# Model01_ANAL.net
KiCad netlist of a schematic drawn in EAGLE
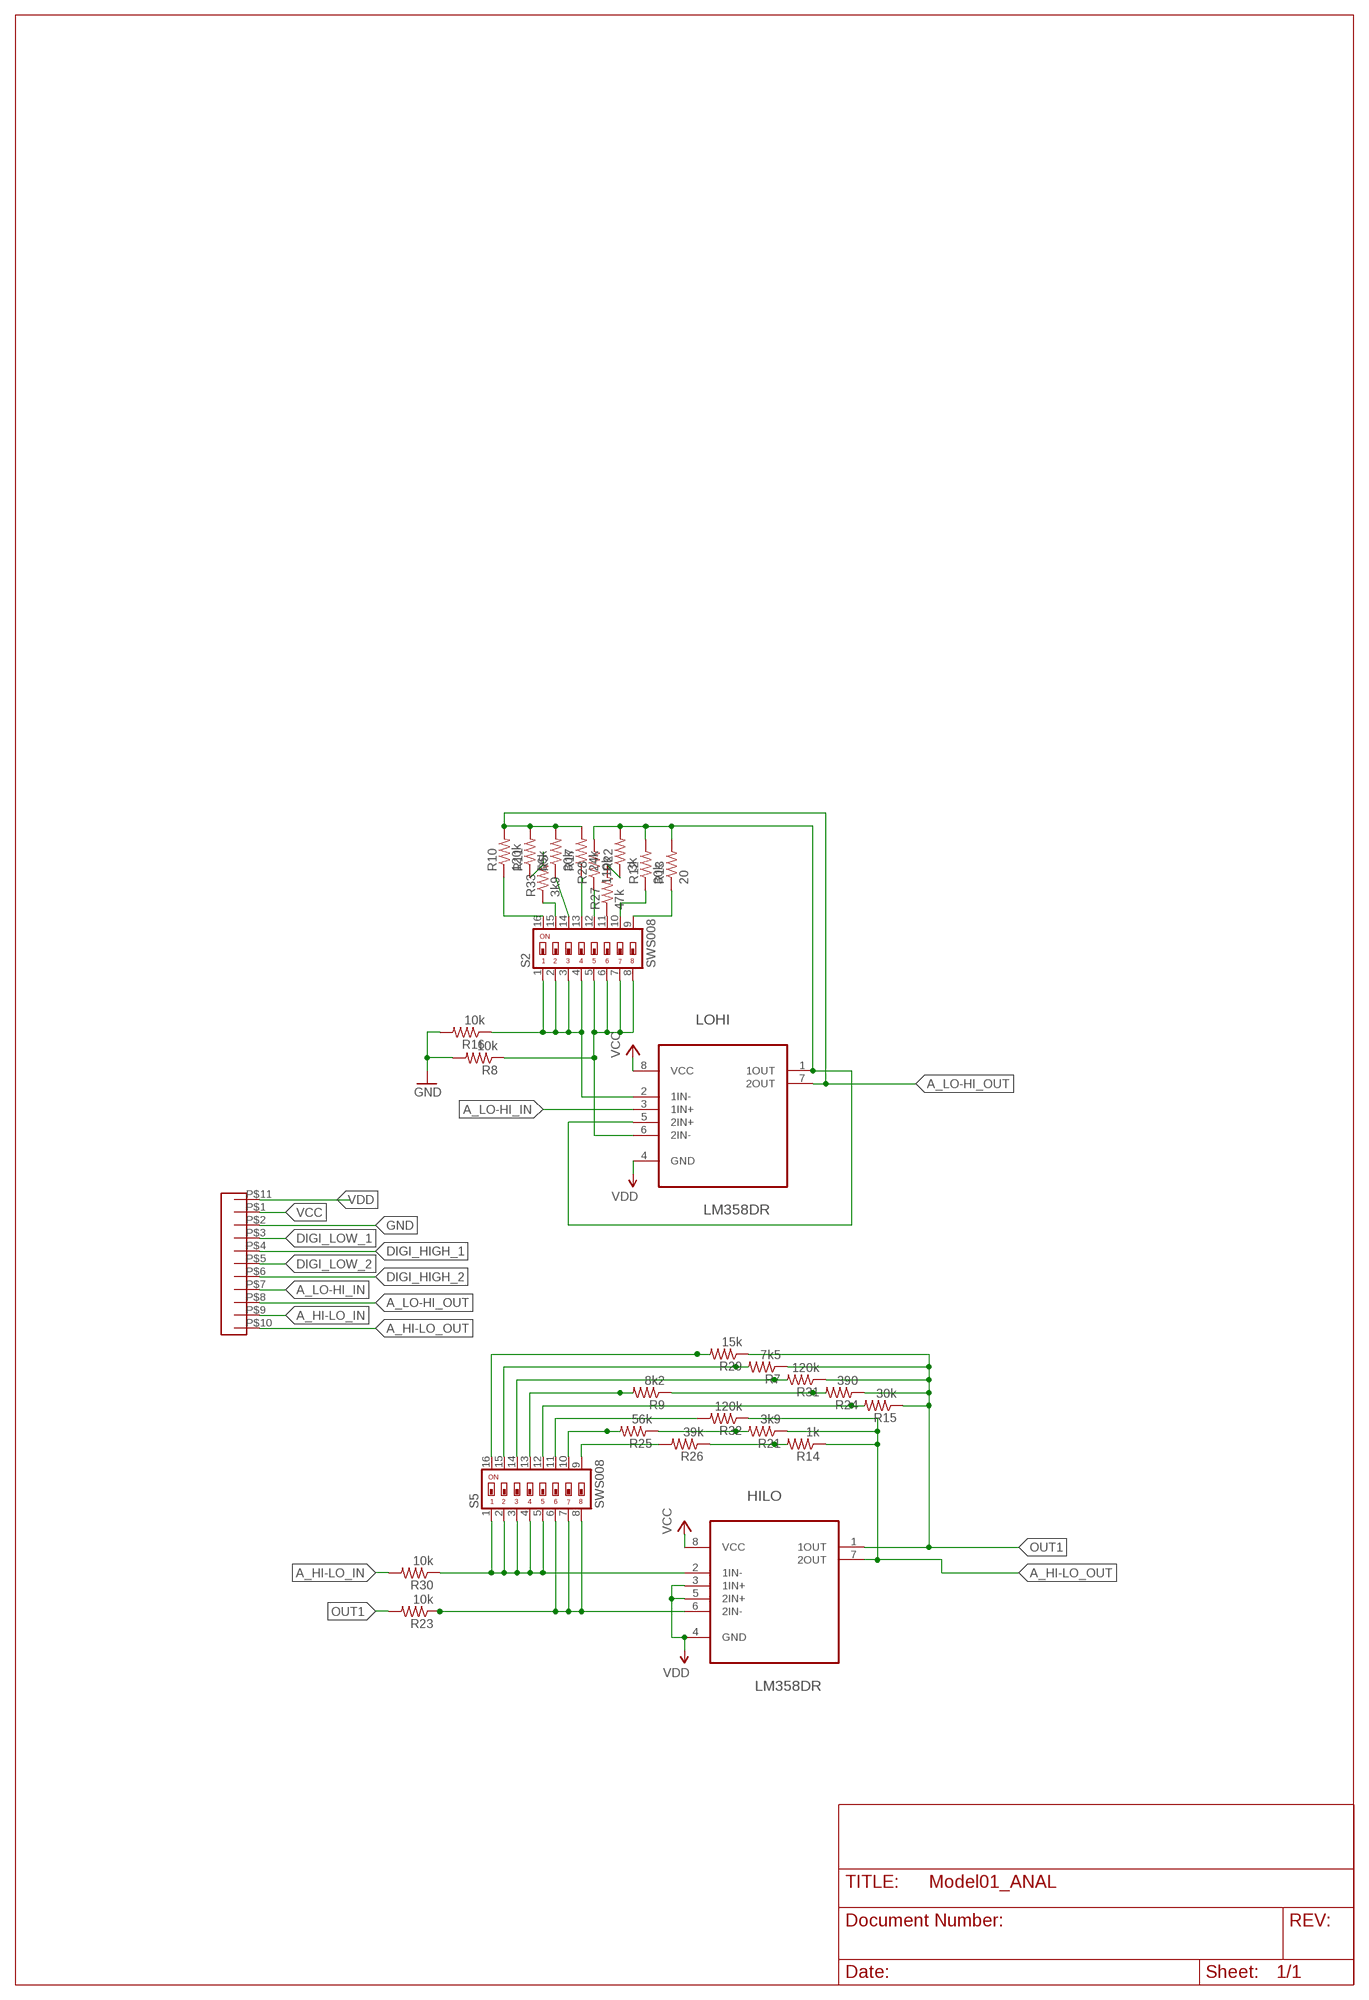
[diagram p0: schematic, sheet 1]

(export (version "E")
  (design (tool "Eeschema 10.0.6"))
  (components
    (comp (ref "HILO")
      (value "LM358DR")
      (footprint "eagle-import:SOIC127P600X175-8N")
      (libsource (lib "eagle-import") (part "LM358DR"))
    )
    (comp (ref "LOHI")
      (value "LM358DR")
      (footprint "eagle-import:SOIC127P600X175-8N")
      (libsource (lib "eagle-import") (part "LM358DR"))
    )
    (comp (ref "R5")
      (value "30k")
      (footprint "eagle-import:R0805")
      (libsource (lib "eagle-import") (part "R-US_R0805"))
    )
    (comp (ref "R7")
      (value "7k5")
      (footprint "eagle-import:R0805")
      (libsource (lib "eagle-import") (part "R-US_R0805"))
    )
    (comp (ref "R8")
      (value "10k")
      (footprint "eagle-import:R0805")
      (libsource (lib "eagle-import") (part "R-US_R0805"))
    )
    (comp (ref "R9")
      (value "8k2")
      (footprint "eagle-import:R0805")
      (libsource (lib "eagle-import") (part "R-US_R0805"))
    )
    (comp (ref "R10")
      (value "120k")
      (footprint "eagle-import:R0805")
      (libsource (lib "eagle-import") (part "R-US_R0805"))
    )
    (comp (ref "R11")
      (value "56k")
      (footprint "eagle-import:R0805")
      (libsource (lib "eagle-import") (part "R-US_R0805"))
    )
    (comp (ref "R12")
      (value "30k")
      (footprint "eagle-import:R0805")
      (libsource (lib "eagle-import") (part "R-US_R0805"))
    )
    (comp (ref "R13")
      (value "20")
      (footprint "eagle-import:R0805")
      (libsource (lib "eagle-import") (part "R-US_R0805"))
    )
    (comp (ref "R14")
      (value "1k")
      (footprint "eagle-import:R0805")
      (libsource (lib "eagle-import") (part "R-US_R0805"))
    )
    (comp (ref "R15")
      (value "30k")
      (footprint "eagle-import:R0805")
      (libsource (lib "eagle-import") (part "R-US_R0805"))
    )
    (comp (ref "R16")
      (value "10k")
      (footprint "eagle-import:R0805")
      (libsource (lib "eagle-import") (part "R-US_R0805"))
    )
    (comp (ref "R17")
      (value "24k")
      (footprint "eagle-import:R0805")
      (libsource (lib "eagle-import") (part "R-US_R0805"))
    )
    (comp (ref "R21")
      (value "3k9")
      (footprint "eagle-import:R0805")
      (libsource (lib "eagle-import") (part "R-US_R0805"))
    )
    (comp (ref "R22")
      (value "3k")
      (footprint "eagle-import:R0805")
      (libsource (lib "eagle-import") (part "R-US_R0805"))
    )
    (comp (ref "R23")
      (value "10k")
      (footprint "eagle-import:R0805")
      (libsource (lib "eagle-import") (part "R-US_R0805"))
    )
    (comp (ref "R24")
      (value "390")
      (footprint "eagle-import:R0805")
      (libsource (lib "eagle-import") (part "R-US_R0805"))
    )
    (comp (ref "R25")
      (value "56k")
      (footprint "eagle-import:R0805")
      (libsource (lib "eagle-import") (part "R-US_R0805"))
    )
    (comp (ref "R26")
      (value "39k")
      (footprint "eagle-import:R0805")
      (libsource (lib "eagle-import") (part "R-US_R0805"))
    )
    (comp (ref "R27")
      (value "47k")
      (footprint "eagle-import:R0805")
      (libsource (lib "eagle-import") (part "R-US_R0805"))
    )
    (comp (ref "R28")
      (value "110k")
      (footprint "eagle-import:R0805")
      (libsource (lib "eagle-import") (part "R-US_R0805"))
    )
    (comp (ref "R29")
      (value "15k")
      (footprint "eagle-import:R0805")
      (libsource (lib "eagle-import") (part "R-US_R0805"))
    )
    (comp (ref "R30")
      (value "10k")
      (footprint "eagle-import:R0805")
      (libsource (lib "eagle-import") (part "R-US_R0805"))
    )
    (comp (ref "R31")
      (value "120k")
      (footprint "eagle-import:R0805")
      (libsource (lib "eagle-import") (part "R-US_R0805"))
    )
    (comp (ref "R32")
      (value "120k")
      (footprint "eagle-import:R0805")
      (libsource (lib "eagle-import") (part "R-US_R0805"))
    )
    (comp (ref "R33")
      (value "3k9")
      (footprint "eagle-import:R0805")
      (libsource (lib "eagle-import") (part "R-US_R0805"))
    )
    (comp (ref "S2")
      (value "SWS008")
      (footprint "eagle-import:SMS-008")
      (libsource (lib "eagle-import") (part "SWS008"))
    )
    (comp (ref "S5")
      (value "SWS008")
      (footprint "eagle-import:SMS-008")
      (libsource (lib "eagle-import") (part "SWS008"))
    )
    (comp (ref "U$1")
      (value "5.08PITCHTERMINAL")
      (footprint "eagle-import:10KPL508")
      (libsource (lib "eagle-import") (part "5.08PITCHTERMINAL"))
    )
  )
  (nets
    (net (code "1") (name "A_HI-LO_IN") (class "Default")
      (node (ref "R30") (pin "2") (pinfunction "2_2") (pintype "passive"))
      (node (ref "U$1") (pin "P$9") (pinfunction "P$9_P$9") (pintype "bidirectional"))
    )
    (net (code "2") (name "A_HI-LO_OUT") (class "Default")
      (node (ref "HILO") (pin "7") (pinfunction "2OUT_7") (pintype "output"))
      (node (ref "R14") (pin "1") (pinfunction "1_1") (pintype "passive"))
      (node (ref "R21") (pin "1") (pinfunction "1_1") (pintype "passive"))
      (node (ref "R32") (pin "1") (pinfunction "1_1") (pintype "passive"))
      (node (ref "U$1") (pin "P$10") (pinfunction "P$10_P$10") (pintype "bidirectional"))
    )
    (net (code "3") (name "A_LO-HI_IN") (class "Default")
      (node (ref "LOHI") (pin "3") (pinfunction "1IN+_3") (pintype "input"))
      (node (ref "U$1") (pin "P$7") (pinfunction "P$7_P$7") (pintype "bidirectional"))
    )
    (net (code "4") (name "A_LO-HI_OUT") (class "Default")
      (node (ref "LOHI") (pin "7") (pinfunction "2OUT_7") (pintype "output"))
      (node (ref "R10") (pin "2") (pinfunction "2_2") (pintype "passive"))
      (node (ref "R11") (pin "2") (pinfunction "2_2") (pintype "passive"))
      (node (ref "R17") (pin "2") (pinfunction "2_2") (pintype "passive"))
      (node (ref "R5") (pin "2") (pinfunction "2_2") (pintype "passive"))
      (node (ref "U$1") (pin "P$8") (pinfunction "P$8_P$8") (pintype "bidirectional"))
    )
    (net (code "5") (name "DIGI_HIGH_1") (class "Default")
      (node (ref "U$1") (pin "P$4") (pinfunction "P$4_P$4") (pintype "bidirectional"))
    )
    (net (code "6") (name "DIGI_HIGH_2") (class "Default")
      (node (ref "U$1") (pin "P$6") (pinfunction "P$6_P$6") (pintype "bidirectional"))
    )
    (net (code "7") (name "DIGI_LOW_1") (class "Default")
      (node (ref "U$1") (pin "P$3") (pinfunction "P$3_P$3") (pintype "bidirectional"))
    )
    (net (code "8") (name "DIGI_LOW_2") (class "Default")
      (node (ref "U$1") (pin "P$5") (pinfunction "P$5_P$5") (pintype "bidirectional"))
    )
    (net (code "9") (name "GND") (class "Default")
      (node (ref "R16") (pin "2") (pinfunction "2_2") (pintype "passive"))
      (node (ref "R8") (pin "2") (pinfunction "2_2") (pintype "passive"))
      (node (ref "U$1") (pin "P$2") (pinfunction "P$2_P$2") (pintype "bidirectional"))
    )
    (net (code "10") (name "Net-(HILO-1IN-)") (class "Default")
      (node (ref "HILO") (pin "2") (pinfunction "1IN-_2") (pintype "input"))
      (node (ref "R30") (pin "1") (pinfunction "1_1") (pintype "passive"))
      (node (ref "S5") (pin "1") (pinfunction "1_1") (pintype "passive"))
      (node (ref "S5") (pin "2") (pinfunction "2_2") (pintype "passive"))
      (node (ref "S5") (pin "3") (pinfunction "3_3") (pintype "passive"))
      (node (ref "S5") (pin "4") (pinfunction "4_4") (pintype "passive"))
      (node (ref "S5") (pin "5") (pinfunction "5_5") (pintype "passive"))
    )
    (net (code "11") (name "Net-(HILO-2IN-)") (class "Default")
      (node (ref "HILO") (pin "6") (pinfunction "2IN-_6") (pintype "input"))
      (node (ref "R23") (pin "1") (pinfunction "1_1") (pintype "passive"))
      (node (ref "S5") (pin "6") (pinfunction "6_6") (pintype "passive"))
      (node (ref "S5") (pin "7") (pinfunction "7_7") (pintype "passive"))
      (node (ref "S5") (pin "8") (pinfunction "8_8") (pintype "passive"))
    )
    (net (code "12") (name "Net-(LOHI-1IN-)") (class "Default")
      (node (ref "LOHI") (pin "2") (pinfunction "1IN-_2") (pintype "input"))
      (node (ref "R16") (pin "1") (pinfunction "1_1") (pintype "passive"))
      (node (ref "S2") (pin "1") (pinfunction "1_1") (pintype "passive"))
      (node (ref "S2") (pin "2") (pinfunction "2_2") (pintype "passive"))
      (node (ref "S2") (pin "3") (pinfunction "3_3") (pintype "passive"))
      (node (ref "S2") (pin "4") (pinfunction "4_4") (pintype "passive"))
    )
    (net (code "13") (name "Net-(LOHI-1OUT)") (class "Default")
      (node (ref "LOHI") (pin "1") (pinfunction "1OUT_1") (pintype "output"))
      (node (ref "LOHI") (pin "5") (pinfunction "2IN+_5") (pintype "input"))
      (node (ref "R12") (pin "2") (pinfunction "2_2") (pintype "passive"))
      (node (ref "R13") (pin "2") (pinfunction "2_2") (pintype "passive"))
      (node (ref "R22") (pin "2") (pinfunction "2_2") (pintype "passive"))
      (node (ref "R28") (pin "2") (pinfunction "2_2") (pintype "passive"))
    )
    (net (code "14") (name "Net-(LOHI-2IN-)") (class "Default")
      (node (ref "LOHI") (pin "6") (pinfunction "2IN-_6") (pintype "input"))
      (node (ref "R8") (pin "1") (pinfunction "1_1") (pintype "passive"))
      (node (ref "S2") (pin "5") (pinfunction "5_5") (pintype "passive"))
      (node (ref "S2") (pin "6") (pinfunction "6_6") (pintype "passive"))
      (node (ref "S2") (pin "7") (pinfunction "7_7") (pintype "passive"))
      (node (ref "S2") (pin "8") (pinfunction "8_8") (pintype "passive"))
    )
    (net (code "15") (name "Net-(R5-Pad1)") (class "Default")
      (node (ref "R5") (pin "1") (pinfunction "1_1") (pintype "passive"))
      (node (ref "S2") (pin "14") (pinfunction "14_14") (pintype "passive"))
    )
    (net (code "16") (name "Net-(R7-Pad2)") (class "Default")
      (node (ref "R7") (pin "2") (pinfunction "2_2") (pintype "passive"))
      (node (ref "S5") (pin "15") (pinfunction "15_15") (pintype "passive"))
    )
    (net (code "17") (name "Net-(R9-Pad2)") (class "Default")
      (node (ref "R9") (pin "2") (pinfunction "2_2") (pintype "passive"))
      (node (ref "S5") (pin "13") (pinfunction "13_13") (pintype "passive"))
    )
    (net (code "18") (name "Net-(R10-Pad1)") (class "Default")
      (node (ref "R10") (pin "1") (pinfunction "1_1") (pintype "passive"))
      (node (ref "S2") (pin "16") (pinfunction "16_16") (pintype "passive"))
    )
    (net (code "19") (name "Net-(R11-Pad1)") (class "Default")
      (node (ref "R11") (pin "1") (pinfunction "1_1") (pintype "passive"))
      (node (ref "R33") (pin "2") (pinfunction "2_2") (pintype "passive"))
    )
    (net (code "20") (name "Net-(R12-Pad1)") (class "Default")
      (node (ref "R12") (pin "1") (pinfunction "1_1") (pintype "passive"))
      (node (ref "S2") (pin "10") (pinfunction "10_10") (pintype "passive"))
    )
    (net (code "21") (name "Net-(R13-Pad1)") (class "Default")
      (node (ref "R13") (pin "1") (pinfunction "1_1") (pintype "passive"))
      (node (ref "S2") (pin "9") (pinfunction "9_9") (pintype "passive"))
    )
    (net (code "22") (name "Net-(R14-Pad2)") (class "Default")
      (node (ref "R14") (pin "2") (pinfunction "2_2") (pintype "passive"))
      (node (ref "R26") (pin "1") (pinfunction "1_1") (pintype "passive"))
    )
    (net (code "23") (name "Net-(R15-Pad2)") (class "Default")
      (node (ref "R15") (pin "2") (pinfunction "2_2") (pintype "passive"))
      (node (ref "S5") (pin "12") (pinfunction "12_12") (pintype "passive"))
    )
    (net (code "24") (name "Net-(R17-Pad1)") (class "Default")
      (node (ref "R17") (pin "1") (pinfunction "1_1") (pintype "passive"))
      (node (ref "S2") (pin "13") (pinfunction "13_13") (pintype "passive"))
    )
    (net (code "25") (name "Net-(R21-Pad2)") (class "Default")
      (node (ref "R21") (pin "2") (pinfunction "2_2") (pintype "passive"))
      (node (ref "R25") (pin "1") (pinfunction "1_1") (pintype "passive"))
    )
    (net (code "26") (name "Net-(R22-Pad1)") (class "Default")
      (node (ref "R22") (pin "1") (pinfunction "1_1") (pintype "passive"))
      (node (ref "R27") (pin "2") (pinfunction "2_2") (pintype "passive"))
    )
    (net (code "27") (name "Net-(R24-Pad2)") (class "Default")
      (node (ref "R24") (pin "2") (pinfunction "2_2") (pintype "passive"))
      (node (ref "R9") (pin "1") (pinfunction "1_1") (pintype "passive"))
    )
    (net (code "28") (name "Net-(R25-Pad2)") (class "Default")
      (node (ref "R25") (pin "2") (pinfunction "2_2") (pintype "passive"))
      (node (ref "S5") (pin "10") (pinfunction "10_10") (pintype "passive"))
    )
    (net (code "29") (name "Net-(R26-Pad2)") (class "Default")
      (node (ref "R26") (pin "2") (pinfunction "2_2") (pintype "passive"))
      (node (ref "S5") (pin "9") (pinfunction "9_9") (pintype "passive"))
    )
    (net (code "30") (name "Net-(R27-Pad1)") (class "Default")
      (node (ref "R27") (pin "1") (pinfunction "1_1") (pintype "passive"))
      (node (ref "S2") (pin "11") (pinfunction "11_11") (pintype "passive"))
    )
    (net (code "31") (name "Net-(R28-Pad1)") (class "Default")
      (node (ref "R28") (pin "1") (pinfunction "1_1") (pintype "passive"))
      (node (ref "S2") (pin "12") (pinfunction "12_12") (pintype "passive"))
    )
    (net (code "32") (name "Net-(R29-Pad2)") (class "Default")
      (node (ref "R29") (pin "2") (pinfunction "2_2") (pintype "passive"))
      (node (ref "S5") (pin "16") (pinfunction "16_16") (pintype "passive"))
    )
    (net (code "33") (name "Net-(R31-Pad2)") (class "Default")
      (node (ref "R31") (pin "2") (pinfunction "2_2") (pintype "passive"))
      (node (ref "S5") (pin "14") (pinfunction "14_14") (pintype "passive"))
    )
    (net (code "34") (name "Net-(R32-Pad2)") (class "Default")
      (node (ref "R32") (pin "2") (pinfunction "2_2") (pintype "passive"))
      (node (ref "S5") (pin "11") (pinfunction "11_11") (pintype "passive"))
    )
    (net (code "35") (name "Net-(R33-Pad1)") (class "Default")
      (node (ref "R33") (pin "1") (pinfunction "1_1") (pintype "passive"))
      (node (ref "S2") (pin "15") (pinfunction "15_15") (pintype "passive"))
    )
    (net (code "36") (name "OUT1") (class "Default")
      (node (ref "HILO") (pin "1") (pinfunction "1OUT_1") (pintype "output"))
      (node (ref "R15") (pin "1") (pinfunction "1_1") (pintype "passive"))
      (node (ref "R23") (pin "2") (pinfunction "2_2") (pintype "passive"))
      (node (ref "R24") (pin "1") (pinfunction "1_1") (pintype "passive"))
      (node (ref "R29") (pin "1") (pinfunction "1_1") (pintype "passive"))
      (node (ref "R31") (pin "1") (pinfunction "1_1") (pintype "passive"))
      (node (ref "R7") (pin "1") (pinfunction "1_1") (pintype "passive"))
    )
    (net (code "37") (name "VCC") (class "Default")
      (node (ref "HILO") (pin "8") (pinfunction "VCC_8") (pintype "power_in"))
      (node (ref "LOHI") (pin "8") (pinfunction "VCC_8") (pintype "power_in"))
      (node (ref "U$1") (pin "P$1") (pinfunction "P$1_P$1") (pintype "bidirectional"))
    )
    (net (code "38") (name "VDD") (class "Default")
      (node (ref "HILO") (pin "3") (pinfunction "1IN+_3") (pintype "input"))
      (node (ref "HILO") (pin "4") (pinfunction "GND_4") (pintype "passive"))
      (node (ref "HILO") (pin "5") (pinfunction "2IN+_5") (pintype "input"))
      (node (ref "LOHI") (pin "4") (pinfunction "GND_4") (pintype "passive"))
      (node (ref "U$1") (pin "P$11") (pinfunction "P$11_P$11") (pintype "bidirectional"))
    )
  )
)
